# Matrix_SMD.net
KiCad netlist of a schematic drawn in EAGLE
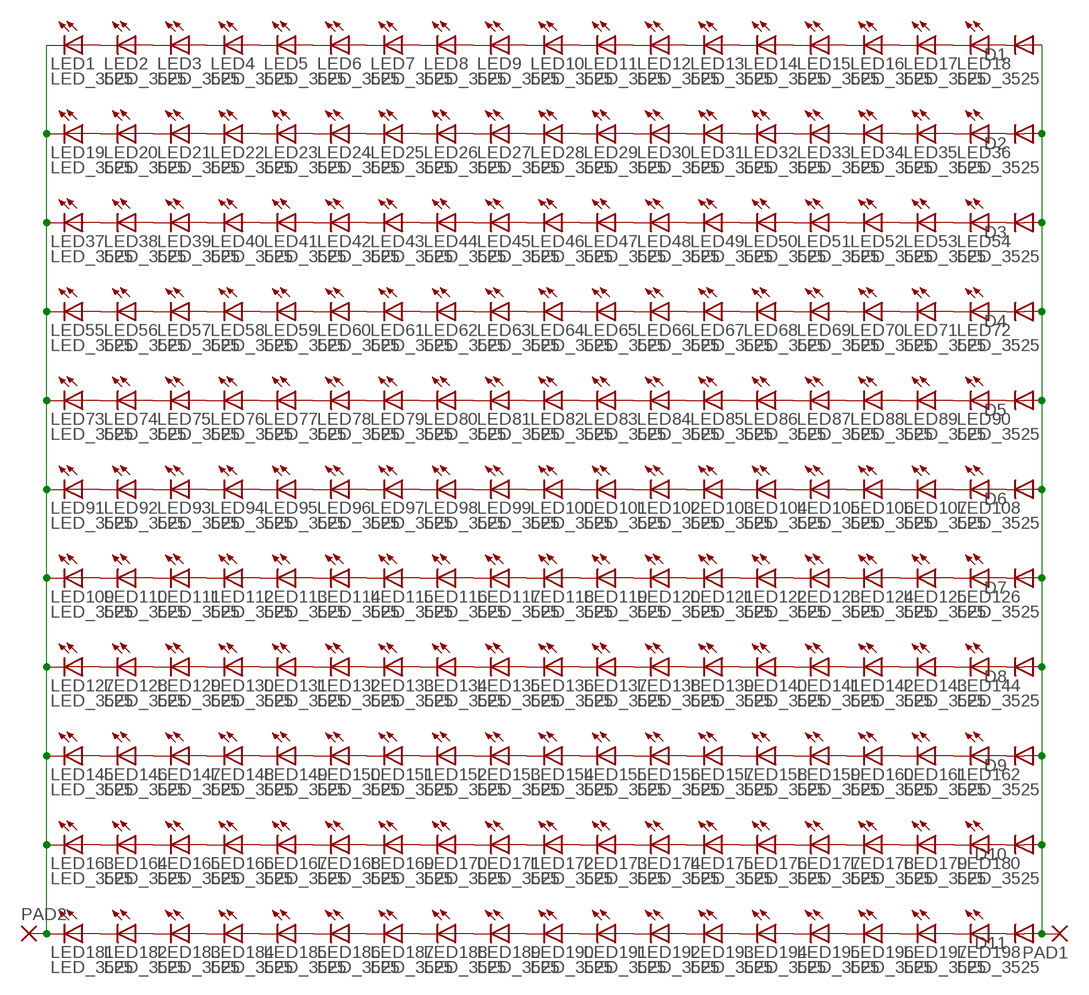
[diagram p0: schematic, sheet 1]

(export (version "E")
  (design (tool "Eeschema 10.0.6"))
  (components
    (comp (ref "D1")
      (value "DIODE-SOD123")
      (footprint "eagle-import:SOD123")
      (libsource (lib "eagle-import") (part "DIODE-SOD123"))
    )
    (comp (ref "D2")
      (value "DIODE-SOD123")
      (footprint "eagle-import:SOD123")
      (libsource (lib "eagle-import") (part "DIODE-SOD123"))
    )
    (comp (ref "D3")
      (value "DIODE-SOD123")
      (footprint "eagle-import:SOD123")
      (libsource (lib "eagle-import") (part "DIODE-SOD123"))
    )
    (comp (ref "D4")
      (value "DIODE-SOD123")
      (footprint "eagle-import:SOD123")
      (libsource (lib "eagle-import") (part "DIODE-SOD123"))
    )
    (comp (ref "D5")
      (value "DIODE-SOD123")
      (footprint "eagle-import:SOD123")
      (libsource (lib "eagle-import") (part "DIODE-SOD123"))
    )
    (comp (ref "D6")
      (value "DIODE-SOD123")
      (footprint "eagle-import:SOD123")
      (libsource (lib "eagle-import") (part "DIODE-SOD123"))
    )
    (comp (ref "D7")
      (value "DIODE-SOD123")
      (footprint "eagle-import:SOD123")
      (libsource (lib "eagle-import") (part "DIODE-SOD123"))
    )
    (comp (ref "D8")
      (value "DIODE-SOD123")
      (footprint "eagle-import:SOD123")
      (libsource (lib "eagle-import") (part "DIODE-SOD123"))
    )
    (comp (ref "D9")
      (value "DIODE-SOD123")
      (footprint "eagle-import:SOD123")
      (libsource (lib "eagle-import") (part "DIODE-SOD123"))
    )
    (comp (ref "D10")
      (value "DIODE-SOD123")
      (footprint "eagle-import:SOD123")
      (libsource (lib "eagle-import") (part "DIODE-SOD123"))
    )
    (comp (ref "D11")
      (value "DIODE-SOD123")
      (footprint "eagle-import:SOD123")
      (libsource (lib "eagle-import") (part "DIODE-SOD123"))
    )
    (comp (ref "LED1")
      (value "LED_3525")
      (footprint "eagle-import:LED3528")
      (libsource (lib "eagle-import") (part "LED_3525"))
    )
    (comp (ref "LED2")
      (value "LED_3525")
      (footprint "eagle-import:LED3528")
      (libsource (lib "eagle-import") (part "LED_3525"))
    )
    (comp (ref "LED3")
      (value "LED_3525")
      (footprint "eagle-import:LED3528")
      (libsource (lib "eagle-import") (part "LED_3525"))
    )
    (comp (ref "LED4")
      (value "LED_3525")
      (footprint "eagle-import:LED3528")
      (libsource (lib "eagle-import") (part "LED_3525"))
    )
    (comp (ref "LED5")
      (value "LED_3525")
      (footprint "eagle-import:LED3528")
      (libsource (lib "eagle-import") (part "LED_3525"))
    )
    (comp (ref "LED6")
      (value "LED_3525")
      (footprint "eagle-import:LED3528")
      (libsource (lib "eagle-import") (part "LED_3525"))
    )
    (comp (ref "LED7")
      (value "LED_3525")
      (footprint "eagle-import:LED3528")
      (libsource (lib "eagle-import") (part "LED_3525"))
    )
    (comp (ref "LED8")
      (value "LED_3525")
      (footprint "eagle-import:LED3528")
      (libsource (lib "eagle-import") (part "LED_3525"))
    )
    (comp (ref "LED9")
      (value "LED_3525")
      (footprint "eagle-import:LED3528")
      (libsource (lib "eagle-import") (part "LED_3525"))
    )
    (comp (ref "LED10")
      (value "LED_3525")
      (footprint "eagle-import:LED3528")
      (libsource (lib "eagle-import") (part "LED_3525"))
    )
    (comp (ref "LED11")
      (value "LED_3525")
      (footprint "eagle-import:LED3528")
      (libsource (lib "eagle-import") (part "LED_3525"))
    )
    (comp (ref "LED12")
      (value "LED_3525")
      (footprint "eagle-import:LED3528")
      (libsource (lib "eagle-import") (part "LED_3525"))
    )
    (comp (ref "LED13")
      (value "LED_3525")
      (footprint "eagle-import:LED3528")
      (libsource (lib "eagle-import") (part "LED_3525"))
    )
    (comp (ref "LED14")
      (value "LED_3525")
      (footprint "eagle-import:LED3528")
      (libsource (lib "eagle-import") (part "LED_3525"))
    )
    (comp (ref "LED15")
      (value "LED_3525")
      (footprint "eagle-import:LED3528")
      (libsource (lib "eagle-import") (part "LED_3525"))
    )
    (comp (ref "LED16")
      (value "LED_3525")
      (footprint "eagle-import:LED3528")
      (libsource (lib "eagle-import") (part "LED_3525"))
    )
    (comp (ref "LED17")
      (value "LED_3525")
      (footprint "eagle-import:LED3528")
      (libsource (lib "eagle-import") (part "LED_3525"))
    )
    (comp (ref "LED18")
      (value "LED_3525")
      (footprint "eagle-import:LED3528")
      (libsource (lib "eagle-import") (part "LED_3525"))
    )
    (comp (ref "LED19")
      (value "LED_3525")
      (footprint "eagle-import:LED3528")
      (libsource (lib "eagle-import") (part "LED_3525"))
    )
    (comp (ref "LED20")
      (value "LED_3525")
      (footprint "eagle-import:LED3528")
      (libsource (lib "eagle-import") (part "LED_3525"))
    )
    (comp (ref "LED21")
      (value "LED_3525")
      (footprint "eagle-import:LED3528")
      (libsource (lib "eagle-import") (part "LED_3525"))
    )
    (comp (ref "LED22")
      (value "LED_3525")
      (footprint "eagle-import:LED3528")
      (libsource (lib "eagle-import") (part "LED_3525"))
    )
    (comp (ref "LED23")
      (value "LED_3525")
      (footprint "eagle-import:LED3528")
      (libsource (lib "eagle-import") (part "LED_3525"))
    )
    (comp (ref "LED24")
      (value "LED_3525")
      (footprint "eagle-import:LED3528")
      (libsource (lib "eagle-import") (part "LED_3525"))
    )
    (comp (ref "LED25")
      (value "LED_3525")
      (footprint "eagle-import:LED3528")
      (libsource (lib "eagle-import") (part "LED_3525"))
    )
    (comp (ref "LED26")
      (value "LED_3525")
      (footprint "eagle-import:LED3528")
      (libsource (lib "eagle-import") (part "LED_3525"))
    )
    (comp (ref "LED27")
      (value "LED_3525")
      (footprint "eagle-import:LED3528")
      (libsource (lib "eagle-import") (part "LED_3525"))
    )
    (comp (ref "LED28")
      (value "LED_3525")
      (footprint "eagle-import:LED3528")
      (libsource (lib "eagle-import") (part "LED_3525"))
    )
    (comp (ref "LED29")
      (value "LED_3525")
      (footprint "eagle-import:LED3528")
      (libsource (lib "eagle-import") (part "LED_3525"))
    )
    (comp (ref "LED30")
      (value "LED_3525")
      (footprint "eagle-import:LED3528")
      (libsource (lib "eagle-import") (part "LED_3525"))
    )
    (comp (ref "LED31")
      (value "LED_3525")
      (footprint "eagle-import:LED3528")
      (libsource (lib "eagle-import") (part "LED_3525"))
    )
    (comp (ref "LED32")
      (value "LED_3525")
      (footprint "eagle-import:LED3528")
      (libsource (lib "eagle-import") (part "LED_3525"))
    )
    (comp (ref "LED33")
      (value "LED_3525")
      (footprint "eagle-import:LED3528")
      (libsource (lib "eagle-import") (part "LED_3525"))
    )
    (comp (ref "LED34")
      (value "LED_3525")
      (footprint "eagle-import:LED3528")
      (libsource (lib "eagle-import") (part "LED_3525"))
    )
    (comp (ref "LED35")
      (value "LED_3525")
      (footprint "eagle-import:LED3528")
      (libsource (lib "eagle-import") (part "LED_3525"))
    )
    (comp (ref "LED36")
      (value "LED_3525")
      (footprint "eagle-import:LED3528")
      (libsource (lib "eagle-import") (part "LED_3525"))
    )
    (comp (ref "LED37")
      (value "LED_3525")
      (footprint "eagle-import:LED3528")
      (libsource (lib "eagle-import") (part "LED_3525"))
    )
    (comp (ref "LED38")
      (value "LED_3525")
      (footprint "eagle-import:LED3528")
      (libsource (lib "eagle-import") (part "LED_3525"))
    )
    (comp (ref "LED39")
      (value "LED_3525")
      (footprint "eagle-import:LED3528")
      (libsource (lib "eagle-import") (part "LED_3525"))
    )
    (comp (ref "LED40")
      (value "LED_3525")
      (footprint "eagle-import:LED3528")
      (libsource (lib "eagle-import") (part "LED_3525"))
    )
    (comp (ref "LED41")
      (value "LED_3525")
      (footprint "eagle-import:LED3528")
      (libsource (lib "eagle-import") (part "LED_3525"))
    )
    (comp (ref "LED42")
      (value "LED_3525")
      (footprint "eagle-import:LED3528")
      (libsource (lib "eagle-import") (part "LED_3525"))
    )
    (comp (ref "LED43")
      (value "LED_3525")
      (footprint "eagle-import:LED3528")
      (libsource (lib "eagle-import") (part "LED_3525"))
    )
    (comp (ref "LED44")
      (value "LED_3525")
      (footprint "eagle-import:LED3528")
      (libsource (lib "eagle-import") (part "LED_3525"))
    )
    (comp (ref "LED45")
      (value "LED_3525")
      (footprint "eagle-import:LED3528")
      (libsource (lib "eagle-import") (part "LED_3525"))
    )
    (comp (ref "LED46")
      (value "LED_3525")
      (footprint "eagle-import:LED3528")
      (libsource (lib "eagle-import") (part "LED_3525"))
    )
    (comp (ref "LED47")
      (value "LED_3525")
      (footprint "eagle-import:LED3528")
      (libsource (lib "eagle-import") (part "LED_3525"))
    )
    (comp (ref "LED48")
      (value "LED_3525")
      (footprint "eagle-import:LED3528")
      (libsource (lib "eagle-import") (part "LED_3525"))
    )
    (comp (ref "LED49")
      (value "LED_3525")
      (footprint "eagle-import:LED3528")
      (libsource (lib "eagle-import") (part "LED_3525"))
    )
    (comp (ref "LED50")
      (value "LED_3525")
      (footprint "eagle-import:LED3528")
      (libsource (lib "eagle-import") (part "LED_3525"))
    )
    (comp (ref "LED51")
      (value "LED_3525")
      (footprint "eagle-import:LED3528")
      (libsource (lib "eagle-import") (part "LED_3525"))
    )
    (comp (ref "LED52")
      (value "LED_3525")
      (footprint "eagle-import:LED3528")
      (libsource (lib "eagle-import") (part "LED_3525"))
    )
    (comp (ref "LED53")
      (value "LED_3525")
      (footprint "eagle-import:LED3528")
      (libsource (lib "eagle-import") (part "LED_3525"))
    )
    (comp (ref "LED54")
      (value "LED_3525")
      (footprint "eagle-import:LED3528")
      (libsource (lib "eagle-import") (part "LED_3525"))
    )
    (comp (ref "LED55")
      (value "LED_3525")
      (footprint "eagle-import:LED3528")
      (libsource (lib "eagle-import") (part "LED_3525"))
    )
    (comp (ref "LED56")
      (value "LED_3525")
      (footprint "eagle-import:LED3528")
      (libsource (lib "eagle-import") (part "LED_3525"))
    )
    (comp (ref "LED57")
      (value "LED_3525")
      (footprint "eagle-import:LED3528")
      (libsource (lib "eagle-import") (part "LED_3525"))
    )
    (comp (ref "LED58")
      (value "LED_3525")
      (footprint "eagle-import:LED3528")
      (libsource (lib "eagle-import") (part "LED_3525"))
    )
    (comp (ref "LED59")
      (value "LED_3525")
      (footprint "eagle-import:LED3528")
      (libsource (lib "eagle-import") (part "LED_3525"))
    )
    (comp (ref "LED60")
      (value "LED_3525")
      (footprint "eagle-import:LED3528")
      (libsource (lib "eagle-import") (part "LED_3525"))
    )
    (comp (ref "LED61")
      (value "LED_3525")
      (footprint "eagle-import:LED3528")
      (libsource (lib "eagle-import") (part "LED_3525"))
    )
    (comp (ref "LED62")
      (value "LED_3525")
      (footprint "eagle-import:LED3528")
      (libsource (lib "eagle-import") (part "LED_3525"))
    )
    (comp (ref "LED63")
      (value "LED_3525")
      (footprint "eagle-import:LED3528")
      (libsource (lib "eagle-import") (part "LED_3525"))
    )
    (comp (ref "LED64")
      (value "LED_3525")
      (footprint "eagle-import:LED3528")
      (libsource (lib "eagle-import") (part "LED_3525"))
    )
    (comp (ref "LED65")
      (value "LED_3525")
      (footprint "eagle-import:LED3528")
      (libsource (lib "eagle-import") (part "LED_3525"))
    )
    (comp (ref "LED66")
      (value "LED_3525")
      (footprint "eagle-import:LED3528")
      (libsource (lib "eagle-import") (part "LED_3525"))
    )
    (comp (ref "LED67")
      (value "LED_3525")
      (footprint "eagle-import:LED3528")
      (libsource (lib "eagle-import") (part "LED_3525"))
    )
    (comp (ref "LED68")
      (value "LED_3525")
      (footprint "eagle-import:LED3528")
      (libsource (lib "eagle-import") (part "LED_3525"))
    )
    (comp (ref "LED69")
      (value "LED_3525")
      (footprint "eagle-import:LED3528")
      (libsource (lib "eagle-import") (part "LED_3525"))
    )
    (comp (ref "LED70")
      (value "LED_3525")
      (footprint "eagle-import:LED3528")
      (libsource (lib "eagle-import") (part "LED_3525"))
    )
    (comp (ref "LED71")
      (value "LED_3525")
      (footprint "eagle-import:LED3528")
      (libsource (lib "eagle-import") (part "LED_3525"))
    )
    (comp (ref "LED72")
      (value "LED_3525")
      (footprint "eagle-import:LED3528")
      (libsource (lib "eagle-import") (part "LED_3525"))
    )
    (comp (ref "LED73")
      (value "LED_3525")
      (footprint "eagle-import:LED3528")
      (libsource (lib "eagle-import") (part "LED_3525"))
    )
    (comp (ref "LED74")
      (value "LED_3525")
      (footprint "eagle-import:LED3528")
      (libsource (lib "eagle-import") (part "LED_3525"))
    )
    (comp (ref "LED75")
      (value "LED_3525")
      (footprint "eagle-import:LED3528")
      (libsource (lib "eagle-import") (part "LED_3525"))
    )
    (comp (ref "LED76")
      (value "LED_3525")
      (footprint "eagle-import:LED3528")
      (libsource (lib "eagle-import") (part "LED_3525"))
    )
    (comp (ref "LED77")
      (value "LED_3525")
      (footprint "eagle-import:LED3528")
      (libsource (lib "eagle-import") (part "LED_3525"))
    )
    (comp (ref "LED78")
      (value "LED_3525")
      (footprint "eagle-import:LED3528")
      (libsource (lib "eagle-import") (part "LED_3525"))
    )
    (comp (ref "LED79")
      (value "LED_3525")
      (footprint "eagle-import:LED3528")
      (libsource (lib "eagle-import") (part "LED_3525"))
    )
    (comp (ref "LED80")
      (value "LED_3525")
      (footprint "eagle-import:LED3528")
      (libsource (lib "eagle-import") (part "LED_3525"))
    )
    (comp (ref "LED81")
      (value "LED_3525")
      (footprint "eagle-import:LED3528")
      (libsource (lib "eagle-import") (part "LED_3525"))
    )
    (comp (ref "LED82")
      (value "LED_3525")
      (footprint "eagle-import:LED3528")
      (libsource (lib "eagle-import") (part "LED_3525"))
    )
    (comp (ref "LED83")
      (value "LED_3525")
      (footprint "eagle-import:LED3528")
      (libsource (lib "eagle-import") (part "LED_3525"))
    )
    (comp (ref "LED84")
      (value "LED_3525")
      (footprint "eagle-import:LED3528")
      (libsource (lib "eagle-import") (part "LED_3525"))
    )
    (comp (ref "LED85")
      (value "LED_3525")
      (footprint "eagle-import:LED3528")
      (libsource (lib "eagle-import") (part "LED_3525"))
    )
    (comp (ref "LED86")
      (value "LED_3525")
      (footprint "eagle-import:LED3528")
      (libsource (lib "eagle-import") (part "LED_3525"))
    )
    (comp (ref "LED87")
      (value "LED_3525")
      (footprint "eagle-import:LED3528")
      (libsource (lib "eagle-import") (part "LED_3525"))
    )
    (comp (ref "LED88")
      (value "LED_3525")
      (footprint "eagle-import:LED3528")
      (libsource (lib "eagle-import") (part "LED_3525"))
    )
    (comp (ref "LED89")
      (value "LED_3525")
      (footprint "eagle-import:LED3528")
      (libsource (lib "eagle-import") (part "LED_3525"))
    )
    (comp (ref "LED90")
      (value "LED_3525")
      (footprint "eagle-import:LED3528")
      (libsource (lib "eagle-import") (part "LED_3525"))
    )
    (comp (ref "LED91")
      (value "LED_3525")
      (footprint "eagle-import:LED3528")
      (libsource (lib "eagle-import") (part "LED_3525"))
    )
    (comp (ref "LED92")
      (value "LED_3525")
      (footprint "eagle-import:LED3528")
      (libsource (lib "eagle-import") (part "LED_3525"))
    )
    (comp (ref "LED93")
      (value "LED_3525")
      (footprint "eagle-import:LED3528")
      (libsource (lib "eagle-import") (part "LED_3525"))
    )
    (comp (ref "LED94")
      (value "LED_3525")
      (footprint "eagle-import:LED3528")
      (libsource (lib "eagle-import") (part "LED_3525"))
    )
    (comp (ref "LED95")
      (value "LED_3525")
      (footprint "eagle-import:LED3528")
      (libsource (lib "eagle-import") (part "LED_3525"))
    )
    (comp (ref "LED96")
      (value "LED_3525")
      (footprint "eagle-import:LED3528")
      (libsource (lib "eagle-import") (part "LED_3525"))
    )
    (comp (ref "LED97")
      (value "LED_3525")
      (footprint "eagle-import:LED3528")
      (libsource (lib "eagle-import") (part "LED_3525"))
    )
    (comp (ref "LED98")
      (value "LED_3525")
      (footprint "eagle-import:LED3528")
      (libsource (lib "eagle-import") (part "LED_3525"))
    )
    (comp (ref "LED99")
      (value "LED_3525")
      (footprint "eagle-import:LED3528")
      (libsource (lib "eagle-import") (part "LED_3525"))
    )
    (comp (ref "LED100")
      (value "LED_3525")
      (footprint "eagle-import:LED3528")
      (libsource (lib "eagle-import") (part "LED_3525"))
    )
    (comp (ref "LED101")
      (value "LED_3525")
      (footprint "eagle-import:LED3528")
      (libsource (lib "eagle-import") (part "LED_3525"))
    )
    (comp (ref "LED102")
      (value "LED_3525")
      (footprint "eagle-import:LED3528")
      (libsource (lib "eagle-import") (part "LED_3525"))
    )
    (comp (ref "LED103")
      (value "LED_3525")
      (footprint "eagle-import:LED3528")
      (libsource (lib "eagle-import") (part "LED_3525"))
    )
    (comp (ref "LED104")
      (value "LED_3525")
      (footprint "eagle-import:LED3528")
      (libsource (lib "eagle-import") (part "LED_3525"))
    )
    (comp (ref "LED105")
      (value "LED_3525")
      (footprint "eagle-import:LED3528")
      (libsource (lib "eagle-import") (part "LED_3525"))
    )
    (comp (ref "LED106")
      (value "LED_3525")
      (footprint "eagle-import:LED3528")
      (libsource (lib "eagle-import") (part "LED_3525"))
    )
    (comp (ref "LED107")
      (value "LED_3525")
      (footprint "eagle-import:LED3528")
      (libsource (lib "eagle-import") (part "LED_3525"))
    )
    (comp (ref "LED108")
      (value "LED_3525")
      (footprint "eagle-import:LED3528")
      (libsource (lib "eagle-import") (part "LED_3525"))
    )
    (comp (ref "LED109")
      (value "LED_3525")
      (footprint "eagle-import:LED3528")
      (libsource (lib "eagle-import") (part "LED_3525"))
    )
    (comp (ref "LED110")
      (value "LED_3525")
      (footprint "eagle-import:LED3528")
      (libsource (lib "eagle-import") (part "LED_3525"))
    )
    (comp (ref "LED111")
      (value "LED_3525")
      (footprint "eagle-import:LED3528")
      (libsource (lib "eagle-import") (part "LED_3525"))
    )
    (comp (ref "LED112")
      (value "LED_3525")
      (footprint "eagle-import:LED3528")
      (libsource (lib "eagle-import") (part "LED_3525"))
    )
    (comp (ref "LED113")
      (value "LED_3525")
      (footprint "eagle-import:LED3528")
      (libsource (lib "eagle-import") (part "LED_3525"))
    )
    (comp (ref "LED114")
      (value "LED_3525")
      (footprint "eagle-import:LED3528")
      (libsource (lib "eagle-import") (part "LED_3525"))
    )
    (comp (ref "LED115")
      (value "LED_3525")
      (footprint "eagle-import:LED3528")
      (libsource (lib "eagle-import") (part "LED_3525"))
    )
    (comp (ref "LED116")
      (value "LED_3525")
      (footprint "eagle-import:LED3528")
      (libsource (lib "eagle-import") (part "LED_3525"))
    )
    (comp (ref "LED117")
      (value "LED_3525")
      (footprint "eagle-import:LED3528")
      (libsource (lib "eagle-import") (part "LED_3525"))
    )
    (comp (ref "LED118")
      (value "LED_3525")
      (footprint "eagle-import:LED3528")
      (libsource (lib "eagle-import") (part "LED_3525"))
    )
    (comp (ref "LED119")
      (value "LED_3525")
      (footprint "eagle-import:LED3528")
      (libsource (lib "eagle-import") (part "LED_3525"))
    )
    (comp (ref "LED120")
      (value "LED_3525")
      (footprint "eagle-import:LED3528")
      (libsource (lib "eagle-import") (part "LED_3525"))
    )
    (comp (ref "LED121")
      (value "LED_3525")
      (footprint "eagle-import:LED3528")
      (libsource (lib "eagle-import") (part "LED_3525"))
    )
    (comp (ref "LED122")
      (value "LED_3525")
      (footprint "eagle-import:LED3528")
      (libsource (lib "eagle-import") (part "LED_3525"))
    )
    (comp (ref "LED123")
      (value "LED_3525")
      (footprint "eagle-import:LED3528")
      (libsource (lib "eagle-import") (part "LED_3525"))
    )
    (comp (ref "LED124")
      (value "LED_3525")
      (footprint "eagle-import:LED3528")
      (libsource (lib "eagle-import") (part "LED_3525"))
    )
    (comp (ref "LED125")
      (value "LED_3525")
      (footprint "eagle-import:LED3528")
      (libsource (lib "eagle-import") (part "LED_3525"))
    )
    (comp (ref "LED126")
      (value "LED_3525")
      (footprint "eagle-import:LED3528")
      (libsource (lib "eagle-import") (part "LED_3525"))
    )
    (comp (ref "LED127")
      (value "LED_3525")
      (footprint "eagle-import:LED3528")
      (libsource (lib "eagle-import") (part "LED_3525"))
    )
    (comp (ref "LED128")
      (value "LED_3525")
      (footprint "eagle-import:LED3528")
      (libsource (lib "eagle-import") (part "LED_3525"))
    )
    (comp (ref "LED129")
      (value "LED_3525")
      (footprint "eagle-import:LED3528")
      (libsource (lib "eagle-import") (part "LED_3525"))
    )
    (comp (ref "LED130")
      (value "LED_3525")
      (footprint "eagle-import:LED3528")
      (libsource (lib "eagle-import") (part "LED_3525"))
    )
    (comp (ref "LED131")
      (value "LED_3525")
      (footprint "eagle-import:LED3528")
      (libsource (lib "eagle-import") (part "LED_3525"))
    )
    (comp (ref "LED132")
      (value "LED_3525")
      (footprint "eagle-import:LED3528")
      (libsource (lib "eagle-import") (part "LED_3525"))
    )
    (comp (ref "LED133")
      (value "LED_3525")
      (footprint "eagle-import:LED3528")
      (libsource (lib "eagle-import") (part "LED_3525"))
    )
    (comp (ref "LED134")
      (value "LED_3525")
      (footprint "eagle-import:LED3528")
      (libsource (lib "eagle-import") (part "LED_3525"))
    )
    (comp (ref "LED135")
      (value "LED_3525")
      (footprint "eagle-import:LED3528")
      (libsource (lib "eagle-import") (part "LED_3525"))
    )
    (comp (ref "LED136")
      (value "LED_3525")
      (footprint "eagle-import:LED3528")
      (libsource (lib "eagle-import") (part "LED_3525"))
    )
    (comp (ref "LED137")
      (value "LED_3525")
      (footprint "eagle-import:LED3528")
      (libsource (lib "eagle-import") (part "LED_3525"))
    )
    (comp (ref "LED138")
      (value "LED_3525")
      (footprint "eagle-import:LED3528")
      (libsource (lib "eagle-import") (part "LED_3525"))
    )
    (comp (ref "LED139")
      (value "LED_3525")
      (footprint "eagle-import:LED3528")
      (libsource (lib "eagle-import") (part "LED_3525"))
    )
    (comp (ref "LED140")
      (value "LED_3525")
      (footprint "eagle-import:LED3528")
      (libsource (lib "eagle-import") (part "LED_3525"))
    )
    (comp (ref "LED141")
      (value "LED_3525")
      (footprint "eagle-import:LED3528")
      (libsource (lib "eagle-import") (part "LED_3525"))
    )
    (comp (ref "LED142")
      (value "LED_3525")
      (footprint "eagle-import:LED3528")
      (libsource (lib "eagle-import") (part "LED_3525"))
    )
    (comp (ref "LED143")
      (value "LED_3525")
      (footprint "eagle-import:LED3528")
      (libsource (lib "eagle-import") (part "LED_3525"))
    )
    (comp (ref "LED144")
      (value "LED_3525")
      (footprint "eagle-import:LED3528")
      (libsource (lib "eagle-import") (part "LED_3525"))
    )
    (comp (ref "LED145")
      (value "LED_3525")
      (footprint "eagle-import:LED3528")
      (libsource (lib "eagle-import") (part "LED_3525"))
    )
    (comp (ref "LED146")
      (value "LED_3525")
      (footprint "eagle-import:LED3528")
      (libsource (lib "eagle-import") (part "LED_3525"))
    )
    (comp (ref "LED147")
      (value "LED_3525")
      (footprint "eagle-import:LED3528")
      (libsource (lib "eagle-import") (part "LED_3525"))
    )
    (comp (ref "LED148")
      (value "LED_3525")
      (footprint "eagle-import:LED3528")
      (libsource (lib "eagle-import") (part "LED_3525"))
    )
    (comp (ref "LED149")
      (value "LED_3525")
      (footprint "eagle-import:LED3528")
      (libsource (lib "eagle-import") (part "LED_3525"))
    )
    (comp (ref "LED150")
      (value "LED_3525")
      (footprint "eagle-import:LED3528")
      (libsource (lib "eagle-import") (part "LED_3525"))
    )
    (comp (ref "LED151")
      (value "LED_3525")
      (footprint "eagle-import:LED3528")
      (libsource (lib "eagle-import") (part "LED_3525"))
    )
    (comp (ref "LED152")
      (value "LED_3525")
      (footprint "eagle-import:LED3528")
      (libsource (lib "eagle-import") (part "LED_3525"))
    )
    (comp (ref "LED153")
      (value "LED_3525")
      (footprint "eagle-import:LED3528")
      (libsource (lib "eagle-import") (part "LED_3525"))
    )
    (comp (ref "LED154")
      (value "LED_3525")
      (footprint "eagle-import:LED3528")
      (libsource (lib "eagle-import") (part "LED_3525"))
    )
    (comp (ref "LED155")
      (value "LED_3525")
      (footprint "eagle-import:LED3528")
      (libsource (lib "eagle-import") (part "LED_3525"))
    )
    (comp (ref "LED156")
      (value "LED_3525")
      (footprint "eagle-import:LED3528")
      (libsource (lib "eagle-import") (part "LED_3525"))
    )
    (comp (ref "LED157")
      (value "LED_3525")
      (footprint "eagle-import:LED3528")
      (libsource (lib "eagle-import") (part "LED_3525"))
    )
    (comp (ref "LED158")
      (value "LED_3525")
      (footprint "eagle-import:LED3528")
      (libsource (lib "eagle-import") (part "LED_3525"))
    )
    (comp (ref "LED159")
      (value "LED_3525")
      (footprint "eagle-import:LED3528")
      (libsource (lib "eagle-import") (part "LED_3525"))
    )
    (comp (ref "LED160")
      (value "LED_3525")
      (footprint "eagle-import:LED3528")
      (libsource (lib "eagle-import") (part "LED_3525"))
    )
    (comp (ref "LED161")
      (value "LED_3525")
      (footprint "eagle-import:LED3528")
      (libsource (lib "eagle-import") (part "LED_3525"))
    )
    (comp (ref "LED162")
      (value "LED_3525")
      (footprint "eagle-import:LED3528")
      (libsource (lib "eagle-import") (part "LED_3525"))
    )
    (comp (ref "LED163")
      (value "LED_3525")
      (footprint "eagle-import:LED3528")
      (libsource (lib "eagle-import") (part "LED_3525"))
    )
    (comp (ref "LED164")
      (value "LED_3525")
      (footprint "eagle-import:LED3528")
      (libsource (lib "eagle-import") (part "LED_3525"))
    )
    (comp (ref "LED165")
      (value "LED_3525")
      (footprint "eagle-import:LED3528")
      (libsource (lib "eagle-import") (part "LED_3525"))
    )
    (comp (ref "LED166")
      (value "LED_3525")
      (footprint "eagle-import:LED3528")
      (libsource (lib "eagle-import") (part "LED_3525"))
    )
    (comp (ref "LED167")
      (value "LED_3525")
      (footprint "eagle-import:LED3528")
      (libsource (lib "eagle-import") (part "LED_3525"))
    )
    (comp (ref "LED168")
      (value "LED_3525")
      (footprint "eagle-import:LED3528")
      (libsource (lib "eagle-import") (part "LED_3525"))
    )
    (comp (ref "LED169")
      (value "LED_3525")
      (footprint "eagle-import:LED3528")
      (libsource (lib "eagle-import") (part "LED_3525"))
    )
    (comp (ref "LED170")
      (value "LED_3525")
      (footprint "eagle-import:LED3528")
      (libsource (lib "eagle-import") (part "LED_3525"))
    )
    (comp (ref "LED171")
      (value "LED_3525")
      (footprint "eagle-import:LED3528")
      (libsource (lib "eagle-import") (part "LED_3525"))
    )
    (comp (ref "LED172")
      (value "LED_3525")
      (footprint "eagle-import:LED3528")
      (libsource (lib "eagle-import") (part "LED_3525"))
    )
    (comp (ref "LED173")
      (value "LED_3525")
      (footprint "eagle-import:LED3528")
      (libsource (lib "eagle-import") (part "LED_3525"))
    )
    (comp (ref "LED174")
      (value "LED_3525")
      (footprint "eagle-import:LED3528")
      (libsource (lib "eagle-import") (part "LED_3525"))
    )
    (comp (ref "LED175")
      (value "LED_3525")
      (footprint "eagle-import:LED3528")
      (libsource (lib "eagle-import") (part "LED_3525"))
    )
    (comp (ref "LED176")
      (value "LED_3525")
      (footprint "eagle-import:LED3528")
      (libsource (lib "eagle-import") (part "LED_3525"))
    )
    (comp (ref "LED177")
      (value "LED_3525")
      (footprint "eagle-import:LED3528")
      (libsource (lib "eagle-import") (part "LED_3525"))
    )
    (comp (ref "LED178")
      (value "LED_3525")
      (footprint "eagle-import:LED3528")
      (libsource (lib "eagle-import") (part "LED_3525"))
    )
    (comp (ref "LED179")
      (value "LED_3525")
      (footprint "eagle-import:LED3528")
      (libsource (lib "eagle-import") (part "LED_3525"))
    )
    (comp (ref "LED180")
      (value "LED_3525")
      (footprint "eagle-import:LED3528")
      (libsource (lib "eagle-import") (part "LED_3525"))
    )
    (comp (ref "LED181")
      (value "LED_3525")
      (footprint "eagle-import:LED3528")
      (libsource (lib "eagle-import") (part "LED_3525"))
    )
    (comp (ref "LED182")
      (value "LED_3525")
      (footprint "eagle-import:LED3528")
      (libsource (lib "eagle-import") (part "LED_3525"))
    )
    (comp (ref "LED183")
      (value "LED_3525")
      (footprint "eagle-import:LED3528")
      (libsource (lib "eagle-import") (part "LED_3525"))
    )
    (comp (ref "LED184")
      (value "LED_3525")
      (footprint "eagle-import:LED3528")
      (libsource (lib "eagle-import") (part "LED_3525"))
    )
    (comp (ref "LED185")
      (value "LED_3525")
      (footprint "eagle-import:LED3528")
      (libsource (lib "eagle-import") (part "LED_3525"))
    )
    (comp (ref "LED186")
      (value "LED_3525")
      (footprint "eagle-import:LED3528")
      (libsource (lib "eagle-import") (part "LED_3525"))
    )
    (comp (ref "LED187")
      (value "LED_3525")
      (footprint "eagle-import:LED3528")
      (libsource (lib "eagle-import") (part "LED_3525"))
    )
    (comp (ref "LED188")
      (value "LED_3525")
      (footprint "eagle-import:LED3528")
      (libsource (lib "eagle-import") (part "LED_3525"))
    )
    (comp (ref "LED189")
      (value "LED_3525")
      (footprint "eagle-import:LED3528")
      (libsource (lib "eagle-import") (part "LED_3525"))
    )
    (comp (ref "LED190")
      (value "LED_3525")
      (footprint "eagle-import:LED3528")
      (libsource (lib "eagle-import") (part "LED_3525"))
    )
    (comp (ref "LED191")
      (value "LED_3525")
      (footprint "eagle-import:LED3528")
      (libsource (lib "eagle-import") (part "LED_3525"))
    )
    (comp (ref "LED192")
      (value "LED_3525")
      (footprint "eagle-import:LED3528")
      (libsource (lib "eagle-import") (part "LED_3525"))
    )
    (comp (ref "LED193")
      (value "LED_3525")
      (footprint "eagle-import:LED3528")
      (libsource (lib "eagle-import") (part "LED_3525"))
    )
    (comp (ref "LED194")
      (value "LED_3525")
      (footprint "eagle-import:LED3528")
      (libsource (lib "eagle-import") (part "LED_3525"))
    )
    (comp (ref "LED195")
      (value "LED_3525")
      (footprint "eagle-import:LED3528")
      (libsource (lib "eagle-import") (part "LED_3525"))
    )
    (comp (ref "LED196")
      (value "LED_3525")
      (footprint "eagle-import:LED3528")
      (libsource (lib "eagle-import") (part "LED_3525"))
    )
    (comp (ref "LED197")
      (value "LED_3525")
      (footprint "eagle-import:LED3528")
      (libsource (lib "eagle-import") (part "LED_3525"))
    )
    (comp (ref "LED198")
      (value "LED_3525")
      (footprint "eagle-import:LED3528")
      (libsource (lib "eagle-import") (part "LED_3525"))
    )
    (comp (ref "PAD1")
      (value "3,81/1,4")
      (footprint "eagle-import:3,81_1,4")
      (libsource (lib "eagle-import") (part "3,81/1,4"))
    )
    (comp (ref "PAD2")
      (value "3,81/1,4")
      (footprint "eagle-import:3,81_1,4")
      (libsource (lib "eagle-import") (part "3,81/1,4"))
    )
  )
  (nets
    (net (code "1") (name "Net-(D1-PadC)") (class "Default")
      (node (ref "D1") (pin "C") (pinfunction "C_C") (pintype "passive"))
      (node (ref "LED18") (pin "A") (pinfunction "A_A") (pintype "passive"))
    )
    (net (code "2") (name "Net-(D2-PadC)") (class "Default")
      (node (ref "D2") (pin "C") (pinfunction "C_C") (pintype "passive"))
      (node (ref "LED36") (pin "A") (pinfunction "A_A") (pintype "passive"))
    )
    (net (code "3") (name "Net-(D3-PadC)") (class "Default")
      (node (ref "D3") (pin "C") (pinfunction "C_C") (pintype "passive"))
      (node (ref "LED54") (pin "A") (pinfunction "A_A") (pintype "passive"))
    )
    (net (code "4") (name "Net-(D4-PadC)") (class "Default")
      (node (ref "D4") (pin "C") (pinfunction "C_C") (pintype "passive"))
      (node (ref "LED72") (pin "A") (pinfunction "A_A") (pintype "passive"))
    )
    (net (code "5") (name "Net-(D5-PadC)") (class "Default")
      (node (ref "D5") (pin "C") (pinfunction "C_C") (pintype "passive"))
      (node (ref "LED90") (pin "A") (pinfunction "A_A") (pintype "passive"))
    )
    (net (code "6") (name "Net-(D6-PadC)") (class "Default")
      (node (ref "D6") (pin "C") (pinfunction "C_C") (pintype "passive"))
      (node (ref "LED108") (pin "A") (pinfunction "A_A") (pintype "passive"))
    )
    (net (code "7") (name "Net-(D7-PadC)") (class "Default")
      (node (ref "D7") (pin "C") (pinfunction "C_C") (pintype "passive"))
      (node (ref "LED126") (pin "A") (pinfunction "A_A") (pintype "passive"))
    )
    (net (code "8") (name "Net-(D8-PadC)") (class "Default")
      (node (ref "D8") (pin "C") (pinfunction "C_C") (pintype "passive"))
      (node (ref "LED144") (pin "A") (pinfunction "A_A") (pintype "passive"))
    )
    (net (code "9") (name "Net-(D9-PadC)") (class "Default")
      (node (ref "D9") (pin "C") (pinfunction "C_C") (pintype "passive"))
      (node (ref "LED162") (pin "A") (pinfunction "A_A") (pintype "passive"))
    )
    (net (code "10") (name "Net-(D10-PadC)") (class "Default")
      (node (ref "D10") (pin "C") (pinfunction "C_C") (pintype "passive"))
      (node (ref "LED180") (pin "A") (pinfunction "A_A") (pintype "passive"))
    )
    (net (code "11") (name "Net-(D11-PadC)") (class "Default")
      (node (ref "D11") (pin "C") (pinfunction "C_C") (pintype "passive"))
      (node (ref "LED198") (pin "A") (pinfunction "A_A") (pintype "passive"))
    )
    (net (code "12") (name "Net-(LED1-PadA)") (class "Default")
      (node (ref "LED1") (pin "A") (pinfunction "A_A") (pintype "passive"))
      (node (ref "LED2") (pin "C") (pinfunction "C_C") (pintype "passive"))
    )
    (net (code "13") (name "Net-(LED2-PadA)") (class "Default")
      (node (ref "LED2") (pin "A") (pinfunction "A_A") (pintype "passive"))
      (node (ref "LED3") (pin "C") (pinfunction "C_C") (pintype "passive"))
    )
    (net (code "14") (name "Net-(LED3-PadA)") (class "Default")
      (node (ref "LED3") (pin "A") (pinfunction "A_A") (pintype "passive"))
      (node (ref "LED4") (pin "C") (pinfunction "C_C") (pintype "passive"))
    )
    (net (code "15") (name "Net-(LED4-PadA)") (class "Default")
      (node (ref "LED4") (pin "A") (pinfunction "A_A") (pintype "passive"))
      (node (ref "LED5") (pin "C") (pinfunction "C_C") (pintype "passive"))
    )
    (net (code "16") (name "Net-(LED5-PadA)") (class "Default")
      (node (ref "LED5") (pin "A") (pinfunction "A_A") (pintype "passive"))
      (node (ref "LED6") (pin "C") (pinfunction "C_C") (pintype "passive"))
    )
    (net (code "17") (name "Net-(LED6-PadA)") (class "Default")
      (node (ref "LED6") (pin "A") (pinfunction "A_A") (pintype "passive"))
      (node (ref "LED7") (pin "C") (pinfunction "C_C") (pintype "passive"))
    )
    (net (code "18") (name "Net-(LED7-PadA)") (class "Default")
      (node (ref "LED7") (pin "A") (pinfunction "A_A") (pintype "passive"))
      (node (ref "LED8") (pin "C") (pinfunction "C_C") (pintype "passive"))
    )
    (net (code "19") (name "Net-(LED8-PadA)") (class "Default")
      (node (ref "LED8") (pin "A") (pinfunction "A_A") (pintype "passive"))
      (node (ref "LED9") (pin "C") (pinfunction "C_C") (pintype "passive"))
    )
    (net (code "20") (name "Net-(LED10-PadA)") (class "Default")
      (node (ref "LED10") (pin "A") (pinfunction "A_A") (pintype "passive"))
      (node (ref "LED11") (pin "C") (pinfunction "C_C") (pintype "passive"))
    )
    (net (code "21") (name "Net-(LED10-PadC)") (class "Default")
      (node (ref "LED10") (pin "C") (pinfunction "C_C") (pintype "passive"))
      (node (ref "LED9") (pin "A") (pinfunction "A_A") (pintype "passive"))
    )
    (net (code "22") (name "Net-(LED11-PadA)") (class "Default")
      (node (ref "LED11") (pin "A") (pinfunction "A_A") (pintype "passive"))
      (node (ref "LED12") (pin "C") (pinfunction "C_C") (pintype "passive"))
    )
    (net (code "23") (name "Net-(LED12-PadA)") (class "Default")
      (node (ref "LED12") (pin "A") (pinfunction "A_A") (pintype "passive"))
      (node (ref "LED13") (pin "C") (pinfunction "C_C") (pintype "passive"))
    )
    (net (code "24") (name "Net-(LED13-PadA)") (class "Default")
      (node (ref "LED13") (pin "A") (pinfunction "A_A") (pintype "passive"))
      (node (ref "LED14") (pin "C") (pinfunction "C_C") (pintype "passive"))
    )
    (net (code "25") (name "Net-(LED14-PadA)") (class "Default")
      (node (ref "LED14") (pin "A") (pinfunction "A_A") (pintype "passive"))
      (node (ref "LED15") (pin "C") (pinfunction "C_C") (pintype "passive"))
    )
    (net (code "26") (name "Net-(LED15-PadA)") (class "Default")
      (node (ref "LED15") (pin "A") (pinfunction "A_A") (pintype "passive"))
      (node (ref "LED16") (pin "C") (pinfunction "C_C") (pintype "passive"))
    )
    (net (code "27") (name "Net-(LED16-PadA)") (class "Default")
      (node (ref "LED16") (pin "A") (pinfunction "A_A") (pintype "passive"))
      (node (ref "LED17") (pin "C") (pinfunction "C_C") (pintype "passive"))
    )
    (net (code "28") (name "Net-(LED17-PadA)") (class "Default")
      (node (ref "LED17") (pin "A") (pinfunction "A_A") (pintype "passive"))
      (node (ref "LED18") (pin "C") (pinfunction "C_C") (pintype "passive"))
    )
    (net (code "29") (name "Net-(LED19-PadA)") (class "Default")
      (node (ref "LED19") (pin "A") (pinfunction "A_A") (pintype "passive"))
      (node (ref "LED20") (pin "C") (pinfunction "C_C") (pintype "passive"))
    )
    (net (code "30") (name "Net-(LED20-PadA)") (class "Default")
      (node (ref "LED20") (pin "A") (pinfunction "A_A") (pintype "passive"))
      (node (ref "LED21") (pin "C") (pinfunction "C_C") (pintype "passive"))
    )
    (net (code "31") (name "Net-(LED21-PadA)") (class "Default")
      (node (ref "LED21") (pin "A") (pinfunction "A_A") (pintype "passive"))
      (node (ref "LED22") (pin "C") (pinfunction "C_C") (pintype "passive"))
    )
    (net (code "32") (name "Net-(LED22-PadA)") (class "Default")
      (node (ref "LED22") (pin "A") (pinfunction "A_A") (pintype "passive"))
      (node (ref "LED23") (pin "C") (pinfunction "C_C") (pintype "passive"))
    )
    (net (code "33") (name "Net-(LED23-PadA)") (class "Default")
      (node (ref "LED23") (pin "A") (pinfunction "A_A") (pintype "passive"))
      (node (ref "LED24") (pin "C") (pinfunction "C_C") (pintype "passive"))
    )
    (net (code "34") (name "Net-(LED24-PadA)") (class "Default")
      (node (ref "LED24") (pin "A") (pinfunction "A_A") (pintype "passive"))
      (node (ref "LED25") (pin "C") (pinfunction "C_C") (pintype "passive"))
    )
    (net (code "35") (name "Net-(LED25-PadA)") (class "Default")
      (node (ref "LED25") (pin "A") (pinfunction "A_A") (pintype "passive"))
      (node (ref "LED26") (pin "C") (pinfunction "C_C") (pintype "passive"))
    )
    (net (code "36") (name "Net-(LED26-PadA)") (class "Default")
      (node (ref "LED26") (pin "A") (pinfunction "A_A") (pintype "passive"))
      (node (ref "LED27") (pin "C") (pinfunction "C_C") (pintype "passive"))
    )
    (net (code "37") (name "Net-(LED27-PadA)") (class "Default")
      (node (ref "LED27") (pin "A") (pinfunction "A_A") (pintype "passive"))
      (node (ref "LED28") (pin "C") (pinfunction "C_C") (pintype "passive"))
    )
    (net (code "38") (name "Net-(LED28-PadA)") (class "Default")
      (node (ref "LED28") (pin "A") (pinfunction "A_A") (pintype "passive"))
      (node (ref "LED29") (pin "C") (pinfunction "C_C") (pintype "passive"))
    )
    (net (code "39") (name "Net-(LED29-PadA)") (class "Default")
      (node (ref "LED29") (pin "A") (pinfunction "A_A") (pintype "passive"))
      (node (ref "LED30") (pin "C") (pinfunction "C_C") (pintype "passive"))
    )
    (net (code "40") (name "Net-(LED30-PadA)") (class "Default")
      (node (ref "LED30") (pin "A") (pinfunction "A_A") (pintype "passive"))
      (node (ref "LED31") (pin "C") (pinfunction "C_C") (pintype "passive"))
    )
    (net (code "41") (name "Net-(LED31-PadA)") (class "Default")
      (node (ref "LED31") (pin "A") (pinfunction "A_A") (pintype "passive"))
      (node (ref "LED32") (pin "C") (pinfunction "C_C") (pintype "passive"))
    )
    (net (code "42") (name "Net-(LED32-PadA)") (class "Default")
      (node (ref "LED32") (pin "A") (pinfunction "A_A") (pintype "passive"))
      (node (ref "LED33") (pin "C") (pinfunction "C_C") (pintype "passive"))
    )
    (net (code "43") (name "Net-(LED33-PadA)") (class "Default")
      (node (ref "LED33") (pin "A") (pinfunction "A_A") (pintype "passive"))
      (node (ref "LED34") (pin "C") (pinfunction "C_C") (pintype "passive"))
    )
    (net (code "44") (name "Net-(LED34-PadA)") (class "Default")
      (node (ref "LED34") (pin "A") (pinfunction "A_A") (pintype "passive"))
      (node (ref "LED35") (pin "C") (pinfunction "C_C") (pintype "passive"))
    )
    (net (code "45") (name "Net-(LED35-PadA)") (class "Default")
      (node (ref "LED35") (pin "A") (pinfunction "A_A") (pintype "passive"))
      (node (ref "LED36") (pin "C") (pinfunction "C_C") (pintype "passive"))
    )
    (net (code "46") (name "Net-(LED37-PadA)") (class "Default")
      (node (ref "LED37") (pin "A") (pinfunction "A_A") (pintype "passive"))
      (node (ref "LED38") (pin "C") (pinfunction "C_C") (pintype "passive"))
    )
    (net (code "47") (name "Net-(LED38-PadA)") (class "Default")
      (node (ref "LED38") (pin "A") (pinfunction "A_A") (pintype "passive"))
      (node (ref "LED39") (pin "C") (pinfunction "C_C") (pintype "passive"))
    )
    (net (code "48") (name "Net-(LED39-PadA)") (class "Default")
      (node (ref "LED39") (pin "A") (pinfunction "A_A") (pintype "passive"))
      (node (ref "LED40") (pin "C") (pinfunction "C_C") (pintype "passive"))
    )
    (net (code "49") (name "Net-(LED40-PadA)") (class "Default")
      (node (ref "LED40") (pin "A") (pinfunction "A_A") (pintype "passive"))
      (node (ref "LED41") (pin "C") (pinfunction "C_C") (pintype "passive"))
    )
    (net (code "50") (name "Net-(LED41-PadA)") (class "Default")
      (node (ref "LED41") (pin "A") (pinfunction "A_A") (pintype "passive"))
      (node (ref "LED42") (pin "C") (pinfunction "C_C") (pintype "passive"))
    )
    (net (code "51") (name "Net-(LED42-PadA)") (class "Default")
      (node (ref "LED42") (pin "A") (pinfunction "A_A") (pintype "passive"))
      (node (ref "LED43") (pin "C") (pinfunction "C_C") (pintype "passive"))
    )
    (net (code "52") (name "Net-(LED43-PadA)") (class "Default")
      (node (ref "LED43") (pin "A") (pinfunction "A_A") (pintype "passive"))
      (node (ref "LED44") (pin "C") (pinfunction "C_C") (pintype "passive"))
    )
    (net (code "53") (name "Net-(LED44-PadA)") (class "Default")
      (node (ref "LED44") (pin "A") (pinfunction "A_A") (pintype "passive"))
      (node (ref "LED45") (pin "C") (pinfunction "C_C") (pintype "passive"))
    )
    (net (code "54") (name "Net-(LED45-PadA)") (class "Default")
      (node (ref "LED45") (pin "A") (pinfunction "A_A") (pintype "passive"))
      (node (ref "LED46") (pin "C") (pinfunction "C_C") (pintype "passive"))
    )
    (net (code "55") (name "Net-(LED46-PadA)") (class "Default")
      (node (ref "LED46") (pin "A") (pinfunction "A_A") (pintype "passive"))
      (node (ref "LED47") (pin "C") (pinfunction "C_C") (pintype "passive"))
    )
    (net (code "56") (name "Net-(LED47-PadA)") (class "Default")
      (node (ref "LED47") (pin "A") (pinfunction "A_A") (pintype "passive"))
      (node (ref "LED48") (pin "C") (pinfunction "C_C") (pintype "passive"))
    )
    (net (code "57") (name "Net-(LED48-PadA)") (class "Default")
      (node (ref "LED48") (pin "A") (pinfunction "A_A") (pintype "passive"))
      (node (ref "LED49") (pin "C") (pinfunction "C_C") (pintype "passive"))
    )
    (net (code "58") (name "Net-(LED49-PadA)") (class "Default")
      (node (ref "LED49") (pin "A") (pinfunction "A_A") (pintype "passive"))
      (node (ref "LED50") (pin "C") (pinfunction "C_C") (pintype "passive"))
    )
    (net (code "59") (name "Net-(LED50-PadA)") (class "Default")
      (node (ref "LED50") (pin "A") (pinfunction "A_A") (pintype "passive"))
      (node (ref "LED51") (pin "C") (pinfunction "C_C") (pintype "passive"))
    )
    (net (code "60") (name "Net-(LED51-PadA)") (class "Default")
      (node (ref "LED51") (pin "A") (pinfunction "A_A") (pintype "passive"))
      (node (ref "LED52") (pin "C") (pinfunction "C_C") (pintype "passive"))
    )
    (net (code "61") (name "Net-(LED52-PadA)") (class "Default")
      (node (ref "LED52") (pin "A") (pinfunction "A_A") (pintype "passive"))
      (node (ref "LED53") (pin "C") (pinfunction "C_C") (pintype "passive"))
    )
    (net (code "62") (name "Net-(LED53-PadA)") (class "Default")
      (node (ref "LED53") (pin "A") (pinfunction "A_A") (pintype "passive"))
      (node (ref "LED54") (pin "C") (pinfunction "C_C") (pintype "passive"))
    )
    (net (code "63") (name "Net-(LED55-PadA)") (class "Default")
      (node (ref "LED55") (pin "A") (pinfunction "A_A") (pintype "passive"))
      (node (ref "LED56") (pin "C") (pinfunction "C_C") (pintype "passive"))
    )
    (net (code "64") (name "Net-(LED56-PadA)") (class "Default")
      (node (ref "LED56") (pin "A") (pinfunction "A_A") (pintype "passive"))
      (node (ref "LED57") (pin "C") (pinfunction "C_C") (pintype "passive"))
    )
    (net (code "65") (name "Net-(LED57-PadA)") (class "Default")
      (node (ref "LED57") (pin "A") (pinfunction "A_A") (pintype "passive"))
      (node (ref "LED58") (pin "C") (pinfunction "C_C") (pintype "passive"))
    )
    (net (code "66") (name "Net-(LED58-PadA)") (class "Default")
      (node (ref "LED58") (pin "A") (pinfunction "A_A") (pintype "passive"))
      (node (ref "LED59") (pin "C") (pinfunction "C_C") (pintype "passive"))
    )
    (net (code "67") (name "Net-(LED59-PadA)") (class "Default")
      (node (ref "LED59") (pin "A") (pinfunction "A_A") (pintype "passive"))
      (node (ref "LED60") (pin "C") (pinfunction "C_C") (pintype "passive"))
    )
    (net (code "68") (name "Net-(LED60-PadA)") (class "Default")
      (node (ref "LED60") (pin "A") (pinfunction "A_A") (pintype "passive"))
      (node (ref "LED61") (pin "C") (pinfunction "C_C") (pintype "passive"))
    )
    (net (code "69") (name "Net-(LED61-PadA)") (class "Default")
      (node (ref "LED61") (pin "A") (pinfunction "A_A") (pintype "passive"))
      (node (ref "LED62") (pin "C") (pinfunction "C_C") (pintype "passive"))
    )
    (net (code "70") (name "Net-(LED62-PadA)") (class "Default")
      (node (ref "LED62") (pin "A") (pinfunction "A_A") (pintype "passive"))
      (node (ref "LED63") (pin "C") (pinfunction "C_C") (pintype "passive"))
    )
    (net (code "71") (name "Net-(LED63-PadA)") (class "Default")
      (node (ref "LED63") (pin "A") (pinfunction "A_A") (pintype "passive"))
      (node (ref "LED64") (pin "C") (pinfunction "C_C") (pintype "passive"))
    )
    (net (code "72") (name "Net-(LED64-PadA)") (class "Default")
      (node (ref "LED64") (pin "A") (pinfunction "A_A") (pintype "passive"))
      (node (ref "LED65") (pin "C") (pinfunction "C_C") (pintype "passive"))
    )
    (net (code "73") (name "Net-(LED65-PadA)") (class "Default")
      (node (ref "LED65") (pin "A") (pinfunction "A_A") (pintype "passive"))
      (node (ref "LED66") (pin "C") (pinfunction "C_C") (pintype "passive"))
    )
    (net (code "74") (name "Net-(LED66-PadA)") (class "Default")
      (node (ref "LED66") (pin "A") (pinfunction "A_A") (pintype "passive"))
      (node (ref "LED67") (pin "C") (pinfunction "C_C") (pintype "passive"))
    )
    (net (code "75") (name "Net-(LED67-PadA)") (class "Default")
      (node (ref "LED67") (pin "A") (pinfunction "A_A") (pintype "passive"))
      (node (ref "LED68") (pin "C") (pinfunction "C_C") (pintype "passive"))
    )
    (net (code "76") (name "Net-(LED68-PadA)") (class "Default")
      (node (ref "LED68") (pin "A") (pinfunction "A_A") (pintype "passive"))
      (node (ref "LED69") (pin "C") (pinfunction "C_C") (pintype "passive"))
    )
    (net (code "77") (name "Net-(LED69-PadA)") (class "Default")
      (node (ref "LED69") (pin "A") (pinfunction "A_A") (pintype "passive"))
      (node (ref "LED70") (pin "C") (pinfunction "C_C") (pintype "passive"))
    )
    (net (code "78") (name "Net-(LED70-PadA)") (class "Default")
      (node (ref "LED70") (pin "A") (pinfunction "A_A") (pintype "passive"))
      (node (ref "LED71") (pin "C") (pinfunction "C_C") (pintype "passive"))
    )
    (net (code "79") (name "Net-(LED71-PadA)") (class "Default")
      (node (ref "LED71") (pin "A") (pinfunction "A_A") (pintype "passive"))
      (node (ref "LED72") (pin "C") (pinfunction "C_C") (pintype "passive"))
    )
    (net (code "80") (name "Net-(LED73-PadA)") (class "Default")
      (node (ref "LED73") (pin "A") (pinfunction "A_A") (pintype "passive"))
      (node (ref "LED74") (pin "C") (pinfunction "C_C") (pintype "passive"))
    )
    (net (code "81") (name "Net-(LED74-PadA)") (class "Default")
      (node (ref "LED74") (pin "A") (pinfunction "A_A") (pintype "passive"))
      (node (ref "LED75") (pin "C") (pinfunction "C_C") (pintype "passive"))
    )
    (net (code "82") (name "Net-(LED75-PadA)") (class "Default")
      (node (ref "LED75") (pin "A") (pinfunction "A_A") (pintype "passive"))
      (node (ref "LED76") (pin "C") (pinfunction "C_C") (pintype "passive"))
    )
    (net (code "83") (name "Net-(LED76-PadA)") (class "Default")
      (node (ref "LED76") (pin "A") (pinfunction "A_A") (pintype "passive"))
      (node (ref "LED77") (pin "C") (pinfunction "C_C") (pintype "passive"))
    )
    (net (code "84") (name "Net-(LED77-PadA)") (class "Default")
      (node (ref "LED77") (pin "A") (pinfunction "A_A") (pintype "passive"))
      (node (ref "LED78") (pin "C") (pinfunction "C_C") (pintype "passive"))
    )
    (net (code "85") (name "Net-(LED78-PadA)") (class "Default")
      (node (ref "LED78") (pin "A") (pinfunction "A_A") (pintype "passive"))
      (node (ref "LED79") (pin "C") (pinfunction "C_C") (pintype "passive"))
    )
    (net (code "86") (name "Net-(LED79-PadA)") (class "Default")
      (node (ref "LED79") (pin "A") (pinfunction "A_A") (pintype "passive"))
      (node (ref "LED80") (pin "C") (pinfunction "C_C") (pintype "passive"))
    )
    (net (code "87") (name "Net-(LED80-PadA)") (class "Default")
      (node (ref "LED80") (pin "A") (pinfunction "A_A") (pintype "passive"))
      (node (ref "LED81") (pin "C") (pinfunction "C_C") (pintype "passive"))
    )
    (net (code "88") (name "Net-(LED81-PadA)") (class "Default")
      (node (ref "LED81") (pin "A") (pinfunction "A_A") (pintype "passive"))
      (node (ref "LED82") (pin "C") (pinfunction "C_C") (pintype "passive"))
    )
    (net (code "89") (name "Net-(LED82-PadA)") (class "Default")
      (node (ref "LED82") (pin "A") (pinfunction "A_A") (pintype "passive"))
      (node (ref "LED83") (pin "C") (pinfunction "C_C") (pintype "passive"))
    )
    (net (code "90") (name "Net-(LED83-PadA)") (class "Default")
      (node (ref "LED83") (pin "A") (pinfunction "A_A") (pintype "passive"))
      (node (ref "LED84") (pin "C") (pinfunction "C_C") (pintype "passive"))
    )
    (net (code "91") (name "Net-(LED84-PadA)") (class "Default")
      (node (ref "LED84") (pin "A") (pinfunction "A_A") (pintype "passive"))
      (node (ref "LED85") (pin "C") (pinfunction "C_C") (pintype "passive"))
    )
    (net (code "92") (name "Net-(LED85-PadA)") (class "Default")
      (node (ref "LED85") (pin "A") (pinfunction "A_A") (pintype "passive"))
      (node (ref "LED86") (pin "C") (pinfunction "C_C") (pintype "passive"))
    )
    (net (code "93") (name "Net-(LED86-PadA)") (class "Default")
      (node (ref "LED86") (pin "A") (pinfunction "A_A") (pintype "passive"))
      (node (ref "LED87") (pin "C") (pinfunction "C_C") (pintype "passive"))
    )
    (net (code "94") (name "Net-(LED87-PadA)") (class "Default")
      (node (ref "LED87") (pin "A") (pinfunction "A_A") (pintype "passive"))
      (node (ref "LED88") (pin "C") (pinfunction "C_C") (pintype "passive"))
    )
    (net (code "95") (name "Net-(LED88-PadA)") (class "Default")
      (node (ref "LED88") (pin "A") (pinfunction "A_A") (pintype "passive"))
      (node (ref "LED89") (pin "C") (pinfunction "C_C") (pintype "passive"))
    )
    (net (code "96") (name "Net-(LED89-PadA)") (class "Default")
      (node (ref "LED89") (pin "A") (pinfunction "A_A") (pintype "passive"))
      (node (ref "LED90") (pin "C") (pinfunction "C_C") (pintype "passive"))
    )
    (net (code "97") (name "Net-(LED91-PadA)") (class "Default")
      (node (ref "LED91") (pin "A") (pinfunction "A_A") (pintype "passive"))
      (node (ref "LED92") (pin "C") (pinfunction "C_C") (pintype "passive"))
    )
    (net (code "98") (name "Net-(LED92-PadA)") (class "Default")
      (node (ref "LED92") (pin "A") (pinfunction "A_A") (pintype "passive"))
      (node (ref "LED93") (pin "C") (pinfunction "C_C") (pintype "passive"))
    )
    (net (code "99") (name "Net-(LED93-PadA)") (class "Default")
      (node (ref "LED93") (pin "A") (pinfunction "A_A") (pintype "passive"))
      (node (ref "LED94") (pin "C") (pinfunction "C_C") (pintype "passive"))
    )
    (net (code "100") (name "Net-(LED94-PadA)") (class "Default")
      (node (ref "LED94") (pin "A") (pinfunction "A_A") (pintype "passive"))
      (node (ref "LED95") (pin "C") (pinfunction "C_C") (pintype "passive"))
    )
    (net (code "101") (name "Net-(LED95-PadA)") (class "Default")
      (node (ref "LED95") (pin "A") (pinfunction "A_A") (pintype "passive"))
      (node (ref "LED96") (pin "C") (pinfunction "C_C") (pintype "passive"))
    )
    (net (code "102") (name "Net-(LED96-PadA)") (class "Default")
      (node (ref "LED96") (pin "A") (pinfunction "A_A") (pintype "passive"))
      (node (ref "LED97") (pin "C") (pinfunction "C_C") (pintype "passive"))
    )
    (net (code "103") (name "Net-(LED97-PadA)") (class "Default")
      (node (ref "LED97") (pin "A") (pinfunction "A_A") (pintype "passive"))
      (node (ref "LED98") (pin "C") (pinfunction "C_C") (pintype "passive"))
    )
    (net (code "104") (name "Net-(LED98-PadA)") (class "Default")
      (node (ref "LED98") (pin "A") (pinfunction "A_A") (pintype "passive"))
      (node (ref "LED99") (pin "C") (pinfunction "C_C") (pintype "passive"))
    )
    (net (code "105") (name "Net-(LED100-PadA)") (class "Default")
      (node (ref "LED100") (pin "A") (pinfunction "A_A") (pintype "passive"))
      (node (ref "LED101") (pin "C") (pinfunction "C_C") (pintype "passive"))
    )
    (net (code "106") (name "Net-(LED100-PadC)") (class "Default")
      (node (ref "LED100") (pin "C") (pinfunction "C_C") (pintype "passive"))
      (node (ref "LED99") (pin "A") (pinfunction "A_A") (pintype "passive"))
    )
    (net (code "107") (name "Net-(LED101-PadA)") (class "Default")
      (node (ref "LED101") (pin "A") (pinfunction "A_A") (pintype "passive"))
      (node (ref "LED102") (pin "C") (pinfunction "C_C") (pintype "passive"))
    )
    (net (code "108") (name "Net-(LED102-PadA)") (class "Default")
      (node (ref "LED102") (pin "A") (pinfunction "A_A") (pintype "passive"))
      (node (ref "LED103") (pin "C") (pinfunction "C_C") (pintype "passive"))
    )
    (net (code "109") (name "Net-(LED103-PadA)") (class "Default")
      (node (ref "LED103") (pin "A") (pinfunction "A_A") (pintype "passive"))
      (node (ref "LED104") (pin "C") (pinfunction "C_C") (pintype "passive"))
    )
    (net (code "110") (name "Net-(LED104-PadA)") (class "Default")
      (node (ref "LED104") (pin "A") (pinfunction "A_A") (pintype "passive"))
      (node (ref "LED105") (pin "C") (pinfunction "C_C") (pintype "passive"))
    )
    (net (code "111") (name "Net-(LED105-PadA)") (class "Default")
      (node (ref "LED105") (pin "A") (pinfunction "A_A") (pintype "passive"))
      (node (ref "LED106") (pin "C") (pinfunction "C_C") (pintype "passive"))
    )
    (net (code "112") (name "Net-(LED106-PadA)") (class "Default")
      (node (ref "LED106") (pin "A") (pinfunction "A_A") (pintype "passive"))
      (node (ref "LED107") (pin "C") (pinfunction "C_C") (pintype "passive"))
    )
    (net (code "113") (name "Net-(LED107-PadA)") (class "Default")
      (node (ref "LED107") (pin "A") (pinfunction "A_A") (pintype "passive"))
      (node (ref "LED108") (pin "C") (pinfunction "C_C") (pintype "passive"))
    )
    (net (code "114") (name "Net-(LED109-PadA)") (class "Default")
      (node (ref "LED109") (pin "A") (pinfunction "A_A") (pintype "passive"))
      (node (ref "LED110") (pin "C") (pinfunction "C_C") (pintype "passive"))
    )
    (net (code "115") (name "Net-(LED110-PadA)") (class "Default")
      (node (ref "LED110") (pin "A") (pinfunction "A_A") (pintype "passive"))
      (node (ref "LED111") (pin "C") (pinfunction "C_C") (pintype "passive"))
    )
    (net (code "116") (name "Net-(LED111-PadA)") (class "Default")
      (node (ref "LED111") (pin "A") (pinfunction "A_A") (pintype "passive"))
      (node (ref "LED112") (pin "C") (pinfunction "C_C") (pintype "passive"))
    )
    (net (code "117") (name "Net-(LED112-PadA)") (class "Default")
      (node (ref "LED112") (pin "A") (pinfunction "A_A") (pintype "passive"))
      (node (ref "LED113") (pin "C") (pinfunction "C_C") (pintype "passive"))
    )
    (net (code "118") (name "Net-(LED113-PadA)") (class "Default")
      (node (ref "LED113") (pin "A") (pinfunction "A_A") (pintype "passive"))
      (node (ref "LED114") (pin "C") (pinfunction "C_C") (pintype "passive"))
    )
    (net (code "119") (name "Net-(LED114-PadA)") (class "Default")
      (node (ref "LED114") (pin "A") (pinfunction "A_A") (pintype "passive"))
      (node (ref "LED115") (pin "C") (pinfunction "C_C") (pintype "passive"))
    )
    (net (code "120") (name "Net-(LED115-PadA)") (class "Default")
      (node (ref "LED115") (pin "A") (pinfunction "A_A") (pintype "passive"))
      (node (ref "LED116") (pin "C") (pinfunction "C_C") (pintype "passive"))
    )
    (net (code "121") (name "Net-(LED116-PadA)") (class "Default")
      (node (ref "LED116") (pin "A") (pinfunction "A_A") (pintype "passive"))
      (node (ref "LED117") (pin "C") (pinfunction "C_C") (pintype "passive"))
    )
    (net (code "122") (name "Net-(LED117-PadA)") (class "Default")
      (node (ref "LED117") (pin "A") (pinfunction "A_A") (pintype "passive"))
      (node (ref "LED118") (pin "C") (pinfunction "C_C") (pintype "passive"))
    )
    (net (code "123") (name "Net-(LED118-PadA)") (class "Default")
      (node (ref "LED118") (pin "A") (pinfunction "A_A") (pintype "passive"))
      (node (ref "LED119") (pin "C") (pinfunction "C_C") (pintype "passive"))
    )
    (net (code "124") (name "Net-(LED119-PadA)") (class "Default")
      (node (ref "LED119") (pin "A") (pinfunction "A_A") (pintype "passive"))
      (node (ref "LED120") (pin "C") (pinfunction "C_C") (pintype "passive"))
    )
    (net (code "125") (name "Net-(LED120-PadA)") (class "Default")
      (node (ref "LED120") (pin "A") (pinfunction "A_A") (pintype "passive"))
      (node (ref "LED121") (pin "C") (pinfunction "C_C") (pintype "passive"))
    )
    (net (code "126") (name "Net-(LED121-PadA)") (class "Default")
      (node (ref "LED121") (pin "A") (pinfunction "A_A") (pintype "passive"))
      (node (ref "LED122") (pin "C") (pinfunction "C_C") (pintype "passive"))
    )
    (net (code "127") (name "Net-(LED122-PadA)") (class "Default")
      (node (ref "LED122") (pin "A") (pinfunction "A_A") (pintype "passive"))
      (node (ref "LED123") (pin "C") (pinfunction "C_C") (pintype "passive"))
    )
    (net (code "128") (name "Net-(LED123-PadA)") (class "Default")
      (node (ref "LED123") (pin "A") (pinfunction "A_A") (pintype "passive"))
      (node (ref "LED124") (pin "C") (pinfunction "C_C") (pintype "passive"))
    )
    (net (code "129") (name "Net-(LED124-PadA)") (class "Default")
      (node (ref "LED124") (pin "A") (pinfunction "A_A") (pintype "passive"))
      (node (ref "LED125") (pin "C") (pinfunction "C_C") (pintype "passive"))
    )
    (net (code "130") (name "Net-(LED125-PadA)") (class "Default")
      (node (ref "LED125") (pin "A") (pinfunction "A_A") (pintype "passive"))
      (node (ref "LED126") (pin "C") (pinfunction "C_C") (pintype "passive"))
    )
    (net (code "131") (name "Net-(LED127-PadA)") (class "Default")
      (node (ref "LED127") (pin "A") (pinfunction "A_A") (pintype "passive"))
      (node (ref "LED128") (pin "C") (pinfunction "C_C") (pintype "passive"))
    )
    (net (code "132") (name "Net-(LED128-PadA)") (class "Default")
      (node (ref "LED128") (pin "A") (pinfunction "A_A") (pintype "passive"))
      (node (ref "LED129") (pin "C") (pinfunction "C_C") (pintype "passive"))
    )
    (net (code "133") (name "Net-(LED129-PadA)") (class "Default")
      (node (ref "LED129") (pin "A") (pinfunction "A_A") (pintype "passive"))
      (node (ref "LED130") (pin "C") (pinfunction "C_C") (pintype "passive"))
    )
    (net (code "134") (name "Net-(LED130-PadA)") (class "Default")
      (node (ref "LED130") (pin "A") (pinfunction "A_A") (pintype "passive"))
      (node (ref "LED131") (pin "C") (pinfunction "C_C") (pintype "passive"))
    )
    (net (code "135") (name "Net-(LED131-PadA)") (class "Default")
      (node (ref "LED131") (pin "A") (pinfunction "A_A") (pintype "passive"))
      (node (ref "LED132") (pin "C") (pinfunction "C_C") (pintype "passive"))
    )
    (net (code "136") (name "Net-(LED132-PadA)") (class "Default")
      (node (ref "LED132") (pin "A") (pinfunction "A_A") (pintype "passive"))
      (node (ref "LED133") (pin "C") (pinfunction "C_C") (pintype "passive"))
    )
    (net (code "137") (name "Net-(LED133-PadA)") (class "Default")
      (node (ref "LED133") (pin "A") (pinfunction "A_A") (pintype "passive"))
      (node (ref "LED134") (pin "C") (pinfunction "C_C") (pintype "passive"))
    )
    (net (code "138") (name "Net-(LED134-PadA)") (class "Default")
      (node (ref "LED134") (pin "A") (pinfunction "A_A") (pintype "passive"))
      (node (ref "LED135") (pin "C") (pinfunction "C_C") (pintype "passive"))
    )
    (net (code "139") (name "Net-(LED135-PadA)") (class "Default")
      (node (ref "LED135") (pin "A") (pinfunction "A_A") (pintype "passive"))
      (node (ref "LED136") (pin "C") (pinfunction "C_C") (pintype "passive"))
    )
    (net (code "140") (name "Net-(LED136-PadA)") (class "Default")
      (node (ref "LED136") (pin "A") (pinfunction "A_A") (pintype "passive"))
      (node (ref "LED137") (pin "C") (pinfunction "C_C") (pintype "passive"))
    )
    (net (code "141") (name "Net-(LED137-PadA)") (class "Default")
      (node (ref "LED137") (pin "A") (pinfunction "A_A") (pintype "passive"))
      (node (ref "LED138") (pin "C") (pinfunction "C_C") (pintype "passive"))
    )
    (net (code "142") (name "Net-(LED138-PadA)") (class "Default")
      (node (ref "LED138") (pin "A") (pinfunction "A_A") (pintype "passive"))
      (node (ref "LED139") (pin "C") (pinfunction "C_C") (pintype "passive"))
    )
    (net (code "143") (name "Net-(LED139-PadA)") (class "Default")
      (node (ref "LED139") (pin "A") (pinfunction "A_A") (pintype "passive"))
      (node (ref "LED140") (pin "C") (pinfunction "C_C") (pintype "passive"))
    )
    (net (code "144") (name "Net-(LED140-PadA)") (class "Default")
      (node (ref "LED140") (pin "A") (pinfunction "A_A") (pintype "passive"))
      (node (ref "LED141") (pin "C") (pinfunction "C_C") (pintype "passive"))
    )
    (net (code "145") (name "Net-(LED141-PadA)") (class "Default")
      (node (ref "LED141") (pin "A") (pinfunction "A_A") (pintype "passive"))
      (node (ref "LED142") (pin "C") (pinfunction "C_C") (pintype "passive"))
    )
    (net (code "146") (name "Net-(LED142-PadA)") (class "Default")
      (node (ref "LED142") (pin "A") (pinfunction "A_A") (pintype "passive"))
      (node (ref "LED143") (pin "C") (pinfunction "C_C") (pintype "passive"))
    )
    (net (code "147") (name "Net-(LED143-PadA)") (class "Default")
      (node (ref "LED143") (pin "A") (pinfunction "A_A") (pintype "passive"))
      (node (ref "LED144") (pin "C") (pinfunction "C_C") (pintype "passive"))
    )
    (net (code "148") (name "Net-(LED145-PadA)") (class "Default")
      (node (ref "LED145") (pin "A") (pinfunction "A_A") (pintype "passive"))
      (node (ref "LED146") (pin "C") (pinfunction "C_C") (pintype "passive"))
    )
    (net (code "149") (name "Net-(LED146-PadA)") (class "Default")
      (node (ref "LED146") (pin "A") (pinfunction "A_A") (pintype "passive"))
      (node (ref "LED147") (pin "C") (pinfunction "C_C") (pintype "passive"))
    )
    (net (code "150") (name "Net-(LED147-PadA)") (class "Default")
      (node (ref "LED147") (pin "A") (pinfunction "A_A") (pintype "passive"))
      (node (ref "LED148") (pin "C") (pinfunction "C_C") (pintype "passive"))
    )
    (net (code "151") (name "Net-(LED148-PadA)") (class "Default")
      (node (ref "LED148") (pin "A") (pinfunction "A_A") (pintype "passive"))
      (node (ref "LED149") (pin "C") (pinfunction "C_C") (pintype "passive"))
    )
    (net (code "152") (name "Net-(LED149-PadA)") (class "Default")
      (node (ref "LED149") (pin "A") (pinfunction "A_A") (pintype "passive"))
      (node (ref "LED150") (pin "C") (pinfunction "C_C") (pintype "passive"))
    )
    (net (code "153") (name "Net-(LED150-PadA)") (class "Default")
      (node (ref "LED150") (pin "A") (pinfunction "A_A") (pintype "passive"))
      (node (ref "LED151") (pin "C") (pinfunction "C_C") (pintype "passive"))
    )
    (net (code "154") (name "Net-(LED151-PadA)") (class "Default")
      (node (ref "LED151") (pin "A") (pinfunction "A_A") (pintype "passive"))
      (node (ref "LED152") (pin "C") (pinfunction "C_C") (pintype "passive"))
    )
    (net (code "155") (name "Net-(LED152-PadA)") (class "Default")
      (node (ref "LED152") (pin "A") (pinfunction "A_A") (pintype "passive"))
      (node (ref "LED153") (pin "C") (pinfunction "C_C") (pintype "passive"))
    )
    (net (code "156") (name "Net-(LED153-PadA)") (class "Default")
      (node (ref "LED153") (pin "A") (pinfunction "A_A") (pintype "passive"))
      (node (ref "LED154") (pin "C") (pinfunction "C_C") (pintype "passive"))
    )
    (net (code "157") (name "Net-(LED154-PadA)") (class "Default")
      (node (ref "LED154") (pin "A") (pinfunction "A_A") (pintype "passive"))
      (node (ref "LED155") (pin "C") (pinfunction "C_C") (pintype "passive"))
    )
    (net (code "158") (name "Net-(LED155-PadA)") (class "Default")
      (node (ref "LED155") (pin "A") (pinfunction "A_A") (pintype "passive"))
      (node (ref "LED156") (pin "C") (pinfunction "C_C") (pintype "passive"))
    )
    (net (code "159") (name "Net-(LED156-PadA)") (class "Default")
      (node (ref "LED156") (pin "A") (pinfunction "A_A") (pintype "passive"))
      (node (ref "LED157") (pin "C") (pinfunction "C_C") (pintype "passive"))
    )
    (net (code "160") (name "Net-(LED157-PadA)") (class "Default")
      (node (ref "LED157") (pin "A") (pinfunction "A_A") (pintype "passive"))
      (node (ref "LED158") (pin "C") (pinfunction "C_C") (pintype "passive"))
    )
    (net (code "161") (name "Net-(LED158-PadA)") (class "Default")
      (node (ref "LED158") (pin "A") (pinfunction "A_A") (pintype "passive"))
      (node (ref "LED159") (pin "C") (pinfunction "C_C") (pintype "passive"))
    )
    (net (code "162") (name "Net-(LED159-PadA)") (class "Default")
      (node (ref "LED159") (pin "A") (pinfunction "A_A") (pintype "passive"))
      (node (ref "LED160") (pin "C") (pinfunction "C_C") (pintype "passive"))
    )
    (net (code "163") (name "Net-(LED160-PadA)") (class "Default")
      (node (ref "LED160") (pin "A") (pinfunction "A_A") (pintype "passive"))
      (node (ref "LED161") (pin "C") (pinfunction "C_C") (pintype "passive"))
    )
    (net (code "164") (name "Net-(LED161-PadA)") (class "Default")
      (node (ref "LED161") (pin "A") (pinfunction "A_A") (pintype "passive"))
      (node (ref "LED162") (pin "C") (pinfunction "C_C") (pintype "passive"))
    )
    (net (code "165") (name "Net-(LED163-PadA)") (class "Default")
      (node (ref "LED163") (pin "A") (pinfunction "A_A") (pintype "passive"))
      (node (ref "LED164") (pin "C") (pinfunction "C_C") (pintype "passive"))
    )
    (net (code "166") (name "Net-(LED164-PadA)") (class "Default")
      (node (ref "LED164") (pin "A") (pinfunction "A_A") (pintype "passive"))
      (node (ref "LED165") (pin "C") (pinfunction "C_C") (pintype "passive"))
    )
    (net (code "167") (name "Net-(LED165-PadA)") (class "Default")
      (node (ref "LED165") (pin "A") (pinfunction "A_A") (pintype "passive"))
      (node (ref "LED166") (pin "C") (pinfunction "C_C") (pintype "passive"))
    )
    (net (code "168") (name "Net-(LED166-PadA)") (class "Default")
      (node (ref "LED166") (pin "A") (pinfunction "A_A") (pintype "passive"))
      (node (ref "LED167") (pin "C") (pinfunction "C_C") (pintype "passive"))
    )
    (net (code "169") (name "Net-(LED167-PadA)") (class "Default")
      (node (ref "LED167") (pin "A") (pinfunction "A_A") (pintype "passive"))
      (node (ref "LED168") (pin "C") (pinfunction "C_C") (pintype "passive"))
    )
    (net (code "170") (name "Net-(LED168-PadA)") (class "Default")
      (node (ref "LED168") (pin "A") (pinfunction "A_A") (pintype "passive"))
      (node (ref "LED169") (pin "C") (pinfunction "C_C") (pintype "passive"))
    )
    (net (code "171") (name "Net-(LED169-PadA)") (class "Default")
      (node (ref "LED169") (pin "A") (pinfunction "A_A") (pintype "passive"))
      (node (ref "LED170") (pin "C") (pinfunction "C_C") (pintype "passive"))
    )
    (net (code "172") (name "Net-(LED170-PadA)") (class "Default")
      (node (ref "LED170") (pin "A") (pinfunction "A_A") (pintype "passive"))
      (node (ref "LED171") (pin "C") (pinfunction "C_C") (pintype "passive"))
    )
    (net (code "173") (name "Net-(LED171-PadA)") (class "Default")
      (node (ref "LED171") (pin "A") (pinfunction "A_A") (pintype "passive"))
      (node (ref "LED172") (pin "C") (pinfunction "C_C") (pintype "passive"))
    )
    (net (code "174") (name "Net-(LED172-PadA)") (class "Default")
      (node (ref "LED172") (pin "A") (pinfunction "A_A") (pintype "passive"))
      (node (ref "LED173") (pin "C") (pinfunction "C_C") (pintype "passive"))
    )
    (net (code "175") (name "Net-(LED173-PadA)") (class "Default")
      (node (ref "LED173") (pin "A") (pinfunction "A_A") (pintype "passive"))
      (node (ref "LED174") (pin "C") (pinfunction "C_C") (pintype "passive"))
    )
    (net (code "176") (name "Net-(LED174-PadA)") (class "Default")
      (node (ref "LED174") (pin "A") (pinfunction "A_A") (pintype "passive"))
      (node (ref "LED175") (pin "C") (pinfunction "C_C") (pintype "passive"))
    )
    (net (code "177") (name "Net-(LED175-PadA)") (class "Default")
      (node (ref "LED175") (pin "A") (pinfunction "A_A") (pintype "passive"))
      (node (ref "LED176") (pin "C") (pinfunction "C_C") (pintype "passive"))
    )
    (net (code "178") (name "Net-(LED176-PadA)") (class "Default")
      (node (ref "LED176") (pin "A") (pinfunction "A_A") (pintype "passive"))
      (node (ref "LED177") (pin "C") (pinfunction "C_C") (pintype "passive"))
    )
    (net (code "179") (name "Net-(LED177-PadA)") (class "Default")
      (node (ref "LED177") (pin "A") (pinfunction "A_A") (pintype "passive"))
      (node (ref "LED178") (pin "C") (pinfunction "C_C") (pintype "passive"))
    )
    (net (code "180") (name "Net-(LED178-PadA)") (class "Default")
      (node (ref "LED178") (pin "A") (pinfunction "A_A") (pintype "passive"))
      (node (ref "LED179") (pin "C") (pinfunction "C_C") (pintype "passive"))
    )
    (net (code "181") (name "Net-(LED179-PadA)") (class "Default")
      (node (ref "LED179") (pin "A") (pinfunction "A_A") (pintype "passive"))
      (node (ref "LED180") (pin "C") (pinfunction "C_C") (pintype "passive"))
    )
    (net (code "182") (name "Net-(LED181-PadA)") (class "Default")
      (node (ref "LED181") (pin "A") (pinfunction "A_A") (pintype "passive"))
      (node (ref "LED182") (pin "C") (pinfunction "C_C") (pintype "passive"))
    )
    (net (code "183") (name "Net-(LED182-PadA)") (class "Default")
      (node (ref "LED182") (pin "A") (pinfunction "A_A") (pintype "passive"))
      (node (ref "LED183") (pin "C") (pinfunction "C_C") (pintype "passive"))
    )
    (net (code "184") (name "Net-(LED183-PadA)") (class "Default")
      (node (ref "LED183") (pin "A") (pinfunction "A_A") (pintype "passive"))
      (node (ref "LED184") (pin "C") (pinfunction "C_C") (pintype "passive"))
    )
    (net (code "185") (name "Net-(LED184-PadA)") (class "Default")
      (node (ref "LED184") (pin "A") (pinfunction "A_A") (pintype "passive"))
      (node (ref "LED185") (pin "C") (pinfunction "C_C") (pintype "passive"))
    )
    (net (code "186") (name "Net-(LED185-PadA)") (class "Default")
      (node (ref "LED185") (pin "A") (pinfunction "A_A") (pintype "passive"))
      (node (ref "LED186") (pin "C") (pinfunction "C_C") (pintype "passive"))
    )
    (net (code "187") (name "Net-(LED186-PadA)") (class "Default")
      (node (ref "LED186") (pin "A") (pinfunction "A_A") (pintype "passive"))
      (node (ref "LED187") (pin "C") (pinfunction "C_C") (pintype "passive"))
    )
    (net (code "188") (name "Net-(LED187-PadA)") (class "Default")
      (node (ref "LED187") (pin "A") (pinfunction "A_A") (pintype "passive"))
      (node (ref "LED188") (pin "C") (pinfunction "C_C") (pintype "passive"))
    )
    (net (code "189") (name "Net-(LED188-PadA)") (class "Default")
      (node (ref "LED188") (pin "A") (pinfunction "A_A") (pintype "passive"))
      (node (ref "LED189") (pin "C") (pinfunction "C_C") (pintype "passive"))
    )
    (net (code "190") (name "Net-(LED189-PadA)") (class "Default")
      (node (ref "LED189") (pin "A") (pinfunction "A_A") (pintype "passive"))
      (node (ref "LED190") (pin "C") (pinfunction "C_C") (pintype "passive"))
    )
    (net (code "191") (name "Net-(LED190-PadA)") (class "Default")
      (node (ref "LED190") (pin "A") (pinfunction "A_A") (pintype "passive"))
      (node (ref "LED191") (pin "C") (pinfunction "C_C") (pintype "passive"))
    )
    (net (code "192") (name "Net-(LED191-PadA)") (class "Default")
      (node (ref "LED191") (pin "A") (pinfunction "A_A") (pintype "passive"))
      (node (ref "LED192") (pin "C") (pinfunction "C_C") (pintype "passive"))
    )
    (net (code "193") (name "Net-(LED192-PadA)") (class "Default")
      (node (ref "LED192") (pin "A") (pinfunction "A_A") (pintype "passive"))
      (node (ref "LED193") (pin "C") (pinfunction "C_C") (pintype "passive"))
    )
    (net (code "194") (name "Net-(LED193-PadA)") (class "Default")
      (node (ref "LED193") (pin "A") (pinfunction "A_A") (pintype "passive"))
      (node (ref "LED194") (pin "C") (pinfunction "C_C") (pintype "passive"))
    )
    (net (code "195") (name "Net-(LED194-PadA)") (class "Default")
      (node (ref "LED194") (pin "A") (pinfunction "A_A") (pintype "passive"))
      (node (ref "LED195") (pin "C") (pinfunction "C_C") (pintype "passive"))
    )
    (net (code "196") (name "Net-(LED195-PadA)") (class "Default")
      (node (ref "LED195") (pin "A") (pinfunction "A_A") (pintype "passive"))
      (node (ref "LED196") (pin "C") (pinfunction "C_C") (pintype "passive"))
    )
    (net (code "197") (name "Net-(LED196-PadA)") (class "Default")
      (node (ref "LED196") (pin "A") (pinfunction "A_A") (pintype "passive"))
      (node (ref "LED197") (pin "C") (pinfunction "C_C") (pintype "passive"))
    )
    (net (code "198") (name "Net-(LED197-PadA)") (class "Default")
      (node (ref "LED197") (pin "A") (pinfunction "A_A") (pintype "passive"))
      (node (ref "LED198") (pin "C") (pinfunction "C_C") (pintype "passive"))
    )
    (net (code "199") (name "Net-(PAD1-P)") (class "Default")
      (node (ref "D1") (pin "A") (pinfunction "A_A") (pintype "passive"))
      (node (ref "D10") (pin "A") (pinfunction "A_A") (pintype "passive"))
      (node (ref "D11") (pin "A") (pinfunction "A_A") (pintype "passive"))
      (node (ref "D2") (pin "A") (pinfunction "A_A") (pintype "passive"))
      (node (ref "D3") (pin "A") (pinfunction "A_A") (pintype "passive"))
      (node (ref "D4") (pin "A") (pinfunction "A_A") (pintype "passive"))
      (node (ref "D5") (pin "A") (pinfunction "A_A") (pintype "passive"))
      (node (ref "D6") (pin "A") (pinfunction "A_A") (pintype "passive"))
      (node (ref "D7") (pin "A") (pinfunction "A_A") (pintype "passive"))
      (node (ref "D8") (pin "A") (pinfunction "A_A") (pintype "passive"))
      (node (ref "D9") (pin "A") (pinfunction "A_A") (pintype "passive"))
      (node (ref "PAD1") (pin "1") (pinfunction "P_1") (pintype "passive"))
    )
    (net (code "200") (name "Net-(PAD2-P)") (class "Default")
      (node (ref "LED1") (pin "C") (pinfunction "C_C") (pintype "passive"))
      (node (ref "LED109") (pin "C") (pinfunction "C_C") (pintype "passive"))
      (node (ref "LED127") (pin "C") (pinfunction "C_C") (pintype "passive"))
      (node (ref "LED145") (pin "C") (pinfunction "C_C") (pintype "passive"))
      (node (ref "LED163") (pin "C") (pinfunction "C_C") (pintype "passive"))
      (node (ref "LED181") (pin "C") (pinfunction "C_C") (pintype "passive"))
      (node (ref "LED19") (pin "C") (pinfunction "C_C") (pintype "passive"))
      (node (ref "LED37") (pin "C") (pinfunction "C_C") (pintype "passive"))
      (node (ref "LED55") (pin "C") (pinfunction "C_C") (pintype "passive"))
      (node (ref "LED73") (pin "C") (pinfunction "C_C") (pintype "passive"))
      (node (ref "LED91") (pin "C") (pinfunction "C_C") (pintype "passive"))
      (node (ref "PAD2") (pin "1") (pinfunction "P_1") (pintype "passive"))
    )
  )
)
